# LAUNCHXL-F28069_B_1400922_5.net
KiCad netlist of a schematic drawn in Altium Designer
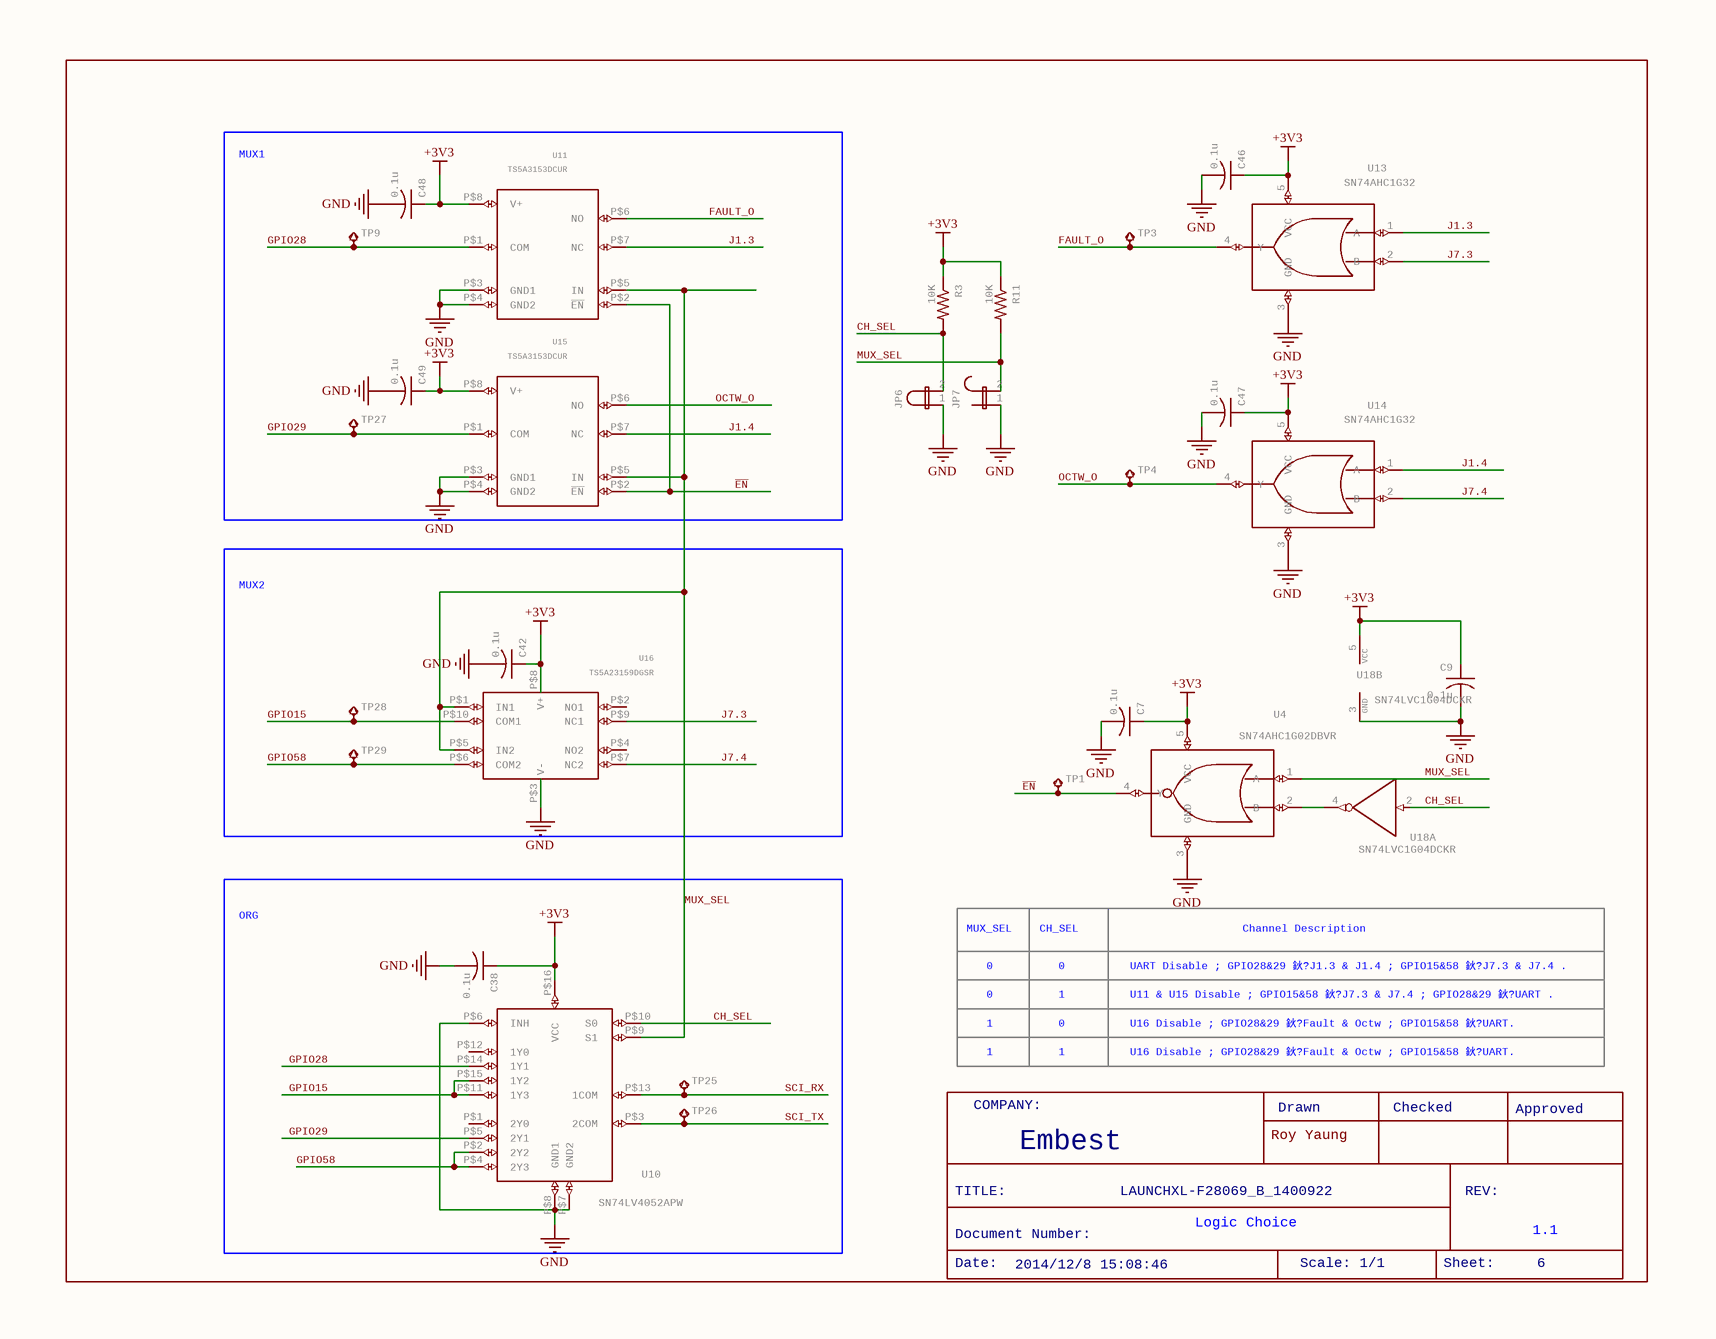
[diagram p0: LAUNCHXL-F28069_B_1400922_5.SchDoc]

(export (version "E")
  (design (tool "Eeschema 10.0.6"))
  (components
    (comp (ref "C7")
      (value "0.1u")
      (footprint "C0402")
      (description "CAPACITOR, American symbol")
      (libsource (lib "rcl") (part "C-USC0402"))
    )
    (comp (ref "C9")
      (value "0.1u")
      (footprint "C0402")
      (description "CAPACITOR, American symbol")
      (libsource (lib "rcl") (part "C-USC0402"))
    )
    (comp (ref "C38")
      (value "0.1u")
      (footprint "C0402")
      (description "CAPACITOR, American symbol")
      (libsource (lib "") (part "C-USC0402_1"))
    )
    (comp (ref "C42")
      (value "0.1u")
      (footprint "C0402")
      (description "CAPACITOR, American symbol")
      (libsource (lib "rcl") (part "C-USC0402"))
    )
    (comp (ref "C46")
      (value "0.1u")
      (footprint "C0402")
      (description "CAPACITOR, American symbol")
      (libsource (lib "rcl") (part "C-USC0402"))
    )
    (comp (ref "C47")
      (value "0.1u")
      (footprint "C0402")
      (description "CAPACITOR, American symbol")
      (libsource (lib "rcl") (part "C-USC0402"))
    )
    (comp (ref "C48")
      (value "0.1u")
      (footprint "C0402")
      (description "CAPACITOR, American symbol")
      (libsource (lib "rcl") (part "C-USC0402"))
    )
    (comp (ref "C49")
      (value "0.1u")
      (footprint "C0402")
      (description "CAPACITOR, American symbol")
      (libsource (lib "rcl") (part "C-USC0402"))
    )
    (comp (ref "JP6")
      (value "JP1ENORM")
      (footprint "JP1")
      (description "JUMPER")
      (libsource (lib "jumper") (part "JP1ENORM"))
    )
    (comp (ref "JP7")
      (value "JP1ENORM")
      (footprint "JP1")
      (description "JUMPER")
      (libsource (lib "jumper") (part "JP1ENORM"))
    )
    (comp (ref "R3")
      (value "10K")
      (footprint "R0402")
      (description "RESISTOR, American symbol")
      (libsource (lib "rcl") (part "R-US_R0402"))
    )
    (comp (ref "R11")
      (value "10K")
      (footprint "R0402")
      (description "RESISTOR, American symbol")
      (libsource (lib "rcl") (part "R-US_R0402"))
    )
    (comp (ref "TP1")
      (value "TESTPAD_TPB1,27")
      (footprint "TESTPAD_B1,27")
      (description "Test pad")
      (fields (field (name "LIBRARYNAME") "RF430FRL152H_EVM_a"))
      (libsource (lib "RF430FRL152H_EVM_a") (part "TESTPAD_TPB1,27"))
    )
    (comp (ref "TP3")
      (value "TESTPAD_TPB1,27")
      (footprint "TESTPAD_B1,27")
      (description "Test pad")
      (fields (field (name "LIBRARYNAME") "RF430FRL152H_EVM_a"))
      (libsource (lib "RF430FRL152H_EVM_a") (part "TESTPAD_TPB1,27"))
    )
    (comp (ref "TP4")
      (value "TESTPAD_TPB1,27")
      (footprint "TESTPAD_B1,27")
      (description "Test pad")
      (fields (field (name "LIBRARYNAME") "RF430FRL152H_EVM_a"))
      (libsource (lib "RF430FRL152H_EVM_a") (part "TESTPAD_TPB1,27"))
    )
    (comp (ref "TP9")
      (value "TESTPAD_TPB1,27")
      (footprint "TESTPAD_B1,27")
      (description "Test pad")
      (fields (field (name "LIBRARYNAME") "RF430FRL152H_EVM_a"))
      (libsource (lib "RF430FRL152H_EVM_a") (part "TESTPAD_TPB1,27"))
    )
    (comp (ref "TP25")
      (value "TESTPAD_TPB1,27")
      (footprint "TESTPAD_B1,27")
      (description "Test pad")
      (fields (field (name "LIBRARYNAME") "RF430FRL152H_EVM_a"))
      (libsource (lib "RF430FRL152H_EVM_a") (part "TESTPAD_TPB1,27"))
    )
    (comp (ref "TP26")
      (value "TESTPAD_TPB1,27")
      (footprint "TESTPAD_B1,27")
      (description "Test pad")
      (fields (field (name "LIBRARYNAME") "RF430FRL152H_EVM_a"))
      (libsource (lib "RF430FRL152H_EVM_a") (part "TESTPAD_TPB1,27"))
    )
    (comp (ref "TP27")
      (value "TESTPAD_TPB1,27")
      (footprint "TESTPAD_B1,27")
      (description "Test pad")
      (fields (field (name "LIBRARYNAME") "RF430FRL152H_EVM_a"))
      (libsource (lib "RF430FRL152H_EVM_a") (part "TESTPAD_TPB1,27"))
    )
    (comp (ref "TP28")
      (value "TESTPAD_TPB1,27")
      (footprint "TESTPAD_B1,27")
      (description "Test pad")
      (fields (field (name "LIBRARYNAME") "RF430FRL152H_EVM_a"))
      (libsource (lib "RF430FRL152H_EVM_a") (part "TESTPAD_TPB1,27"))
    )
    (comp (ref "TP29")
      (value "TESTPAD_TPB1,27")
      (footprint "TESTPAD_B1,27")
      (description "Test pad")
      (fields (field (name "LIBRARYNAME") "RF430FRL152H_EVM_a"))
      (libsource (lib "RF430FRL152H_EVM_a") (part "TESTPAD_TPB1,27"))
    )
    (comp (ref "U$1")
      (value "ROY_JUMPER")
      (footprint "ROY_JUMPER")
      (libsource (lib "roy") (part "ROY_JUMPER"))
    )
    (comp (ref "U$2")
      (value "ROY_JUMPER")
      (footprint "ROY_JUMPER")
      (libsource (lib "roy") (part "ROY_JUMPER"))
    )
    (comp (ref "U4")
      (value "SN74AHC1G02DBVR")
      (footprint "SOT23-5-DBV")
      (libsource (lib "LAUNCHXL-F28027") (part "SN74AHC1G02"))
    )
    (comp (ref "U10")
      (value "SN74LV4052APW")
      (footprint "TSSOP16-PW")
      (libsource (lib "LAUNCHXL-F28027") (part "SN74LV4052APW"))
    )
    (comp (ref "U11")
      (value "TS5A3153DCUR")
      (footprint "TI-DCU8")
      (libsource (lib "LAUNCHXL-F28027") (part "TS5A3153DCUR"))
    )
    (comp (ref "U13")
      (value "SN74AHC1G32")
      (footprint "SOT23-5-DBV")
      (libsource (lib "LAUNCHXL-F28027") (part "SN74AHC1G32"))
    )
    (comp (ref "U14")
      (value "SN74AHC1G32")
      (footprint "SOT23-5-DBV")
      (libsource (lib "LAUNCHXL-F28027") (part "SN74AHC1G32"))
    )
    (comp (ref "U15")
      (value "TS5A3153DCUR")
      (footprint "TI-DCU8")
      (libsource (lib "LAUNCHXL-F28027") (part "TS5A3153DCUR"))
    )
    (comp (ref "U16")
      (value "TS5A23159DGSR")
      (footprint "TI-DGS10")
      (libsource (lib "LAUNCHXL-F28027") (part "TS5A23159DGSR"))
    )
    (comp (ref "U18")
      (value "SN74LVC1G04DCKR")
      (footprint "74XX-LITTLE-DE_SC70-5")
      (description "INVERTER Gate")
      (fields
        (field (name "GND") "GND")
        (field (name "VCC") "VCC")
        (field (name "LIBRARYNAME") "RF430FRL152H_EVM_a")
      )
      (libsource (lib "RF430FRL152H_EVM_a") (part "74XX-LITTLE-DE_74*1G04DCK"))
    )
  )
  (nets
    (net (code "1") (name "+3V3") (class "Default")
      (node (ref "C38") (pin "1") (pinfunction "1_1") (pintype "passive"))
      (node (ref "C42") (pin "1") (pinfunction "1_1") (pintype "passive"))
      (node (ref "C46") (pin "1") (pinfunction "1_1") (pintype "passive"))
      (node (ref "C47") (pin "1") (pinfunction "1_1") (pintype "passive"))
      (node (ref "C48") (pin "1") (pinfunction "1_1") (pintype "passive"))
      (node (ref "C49") (pin "1") (pinfunction "1_1") (pintype "passive"))
      (node (ref "C7") (pin "1") (pinfunction "1_1") (pintype "passive"))
      (node (ref "C9") (pin "1") (pinfunction "1_1") (pintype "passive"))
      (node (ref "R11") (pin "1") (pinfunction "1_1") (pintype "passive"))
      (node (ref "R3") (pin "1") (pinfunction "1_1") (pintype "passive"))
      (node (ref "U10") (pin "P$16") (pinfunction "VCC_P$16") (pintype "bidirectional"))
      (node (ref "U11") (pin "P$8") (pinfunction "V+_P$8") (pintype "bidirectional"))
      (node (ref "U13") (pin "5") (pinfunction "VCC_5") (pintype "bidirectional"))
      (node (ref "U14") (pin "5") (pinfunction "VCC_5") (pintype "bidirectional"))
      (node (ref "U15") (pin "P$8") (pinfunction "V+_P$8") (pintype "bidirectional"))
      (node (ref "U16") (pin "P$8") (pinfunction "V+_P$8") (pintype "bidirectional"))
      (node (ref "U18") (pin "5") (pinfunction "VCC_5") (pintype "power_in"))
      (node (ref "U4") (pin "5") (pinfunction "VCC_5") (pintype "bidirectional"))
    )
    (net (code "2") (name "/CH_SEL") (class "Default")
      (node (ref "JP6") (pin "2") (pinfunction "2_2") (pintype "passive"))
      (node (ref "R3") (pin "2") (pinfunction "2_2") (pintype "passive"))
      (node (ref "U10") (pin "P$10") (pinfunction "S0_P$10") (pintype "bidirectional"))
      (node (ref "U18") (pin "2") (pinfunction "I_2") (pintype "input"))
    )
    (net (code "3") (name "/FAULT_O") (class "Default")
      (node (ref "TP3") (pin "TP") (pinfunction "TP_TP") (pintype "input"))
      (node (ref "U11") (pin "P$6") (pinfunction "NO_P$6") (pintype "bidirectional"))
      (node (ref "U13") (pin "4") (pinfunction "Y_4") (pintype "bidirectional"))
    )
    (net (code "4") (name "/GPIO15") (class "Default")
      (node (ref "TP28") (pin "TP") (pinfunction "TP_TP") (pintype "input"))
      (node (ref "U10") (pin "P$11") (pinfunction "1Y3_P$11") (pintype "bidirectional"))
      (node (ref "U10") (pin "P$15") (pinfunction "1Y2_P$15") (pintype "bidirectional"))
      (node (ref "U16") (pin "P$10") (pinfunction "COM1_P$10") (pintype "bidirectional"))
    )
    (net (code "5") (name "/GPIO28") (class "Default")
      (node (ref "TP9") (pin "TP") (pinfunction "TP_TP") (pintype "input"))
      (node (ref "U10") (pin "P$14") (pinfunction "1Y1_P$14") (pintype "bidirectional"))
      (node (ref "U11") (pin "P$1") (pinfunction "COM_P$1") (pintype "bidirectional"))
    )
    (net (code "6") (name "/GPIO29") (class "Default")
      (node (ref "TP27") (pin "TP") (pinfunction "TP_TP") (pintype "input"))
      (node (ref "U10") (pin "P$5") (pinfunction "2Y1_P$5") (pintype "bidirectional"))
      (node (ref "U15") (pin "P$1") (pinfunction "COM_P$1") (pintype "bidirectional"))
    )
    (net (code "7") (name "/GPIO58") (class "Default")
      (node (ref "TP29") (pin "TP") (pinfunction "TP_TP") (pintype "input"))
      (node (ref "U10") (pin "P$2") (pinfunction "2Y2_P$2") (pintype "bidirectional"))
      (node (ref "U10") (pin "P$4") (pinfunction "2Y3_P$4") (pintype "bidirectional"))
      (node (ref "U16") (pin "P$6") (pinfunction "COM2_P$6") (pintype "bidirectional"))
    )
    (net (code "8") (name "/J1.3") (class "Default")
      (node (ref "U11") (pin "P$7") (pinfunction "NC_P$7") (pintype "bidirectional"))
      (node (ref "U13") (pin "1") (pinfunction "A_1") (pintype "bidirectional"))
    )
    (net (code "9") (name "/J1.4") (class "Default")
      (node (ref "U14") (pin "1") (pinfunction "A_1") (pintype "bidirectional"))
      (node (ref "U15") (pin "P$7") (pinfunction "NC_P$7") (pintype "bidirectional"))
    )
    (net (code "10") (name "/J7.3") (class "Default")
      (node (ref "U13") (pin "2") (pinfunction "B_2") (pintype "bidirectional"))
      (node (ref "U16") (pin "P$9") (pinfunction "NC1_P$9") (pintype "bidirectional"))
    )
    (net (code "11") (name "/J7.4") (class "Default")
      (node (ref "U14") (pin "2") (pinfunction "B_2") (pintype "bidirectional"))
      (node (ref "U16") (pin "P$7") (pinfunction "NC2_P$7") (pintype "bidirectional"))
    )
    (net (code "12") (name "/MUX_SEL") (class "Default")
      (node (ref "JP7") (pin "2") (pinfunction "2_2") (pintype "passive"))
      (node (ref "R11") (pin "2") (pinfunction "2_2") (pintype "passive"))
      (node (ref "U10") (pin "P$9") (pinfunction "S1_P$9") (pintype "bidirectional"))
      (node (ref "U11") (pin "P$5") (pinfunction "IN_P$5") (pintype "bidirectional"))
      (node (ref "U15") (pin "P$5") (pinfunction "IN_P$5") (pintype "bidirectional"))
      (node (ref "U16") (pin "P$1") (pinfunction "IN1_P$1") (pintype "bidirectional"))
      (node (ref "U16") (pin "P$5") (pinfunction "IN2_P$5") (pintype "bidirectional"))
      (node (ref "U4") (pin "1") (pinfunction "A_1") (pintype "bidirectional"))
    )
    (net (code "13") (name "/OCTW_O") (class "Default")
      (node (ref "TP4") (pin "TP") (pinfunction "TP_TP") (pintype "input"))
      (node (ref "U14") (pin "4") (pinfunction "Y_4") (pintype "bidirectional"))
      (node (ref "U15") (pin "P$6") (pinfunction "NO_P$6") (pintype "bidirectional"))
    )
    (net (code "14") (name "/SCI_RX") (class "Default")
      (node (ref "TP25") (pin "TP") (pinfunction "TP_TP") (pintype "input"))
      (node (ref "U10") (pin "P$13") (pinfunction "1COM_P$13") (pintype "bidirectional"))
    )
    (net (code "15") (name "/SCI_TX") (class "Default")
      (node (ref "TP26") (pin "TP") (pinfunction "TP_TP") (pintype "input"))
      (node (ref "U10") (pin "P$3") (pinfunction "2COM_P$3") (pintype "bidirectional"))
    )
    (net (code "16") (name "/~{EN}") (class "Default")
      (node (ref "TP1") (pin "TP") (pinfunction "TP_TP") (pintype "input"))
      (node (ref "U11") (pin "P$2") (pinfunction "~{EN}_P$2") (pintype "bidirectional"))
      (node (ref "U15") (pin "P$2") (pinfunction "~{EN}_P$2") (pintype "bidirectional"))
      (node (ref "U4") (pin "4") (pinfunction "Y_4") (pintype "bidirectional"))
    )
    (net (code "17") (name "GND") (class "Default")
      (node (ref "C38") (pin "2") (pinfunction "2_2") (pintype "passive"))
      (node (ref "C42") (pin "2") (pinfunction "2_2") (pintype "passive"))
      (node (ref "C46") (pin "2") (pinfunction "2_2") (pintype "passive"))
      (node (ref "C47") (pin "2") (pinfunction "2_2") (pintype "passive"))
      (node (ref "C48") (pin "2") (pinfunction "2_2") (pintype "passive"))
      (node (ref "C49") (pin "2") (pinfunction "2_2") (pintype "passive"))
      (node (ref "C7") (pin "2") (pinfunction "2_2") (pintype "passive"))
      (node (ref "C9") (pin "2") (pinfunction "2_2") (pintype "passive"))
      (node (ref "JP6") (pin "1") (pinfunction "1_1") (pintype "passive"))
      (node (ref "JP7") (pin "1") (pinfunction "1_1") (pintype "passive"))
      (node (ref "U10") (pin "P$6") (pinfunction "INH_P$6") (pintype "bidirectional"))
      (node (ref "U10") (pin "P$7") (pinfunction "GND2_P$7") (pintype "bidirectional"))
      (node (ref "U10") (pin "P$8") (pinfunction "GND1_P$8") (pintype "bidirectional"))
      (node (ref "U11") (pin "P$3") (pinfunction "GND1_P$3") (pintype "bidirectional"))
      (node (ref "U11") (pin "P$4") (pinfunction "GND2_P$4") (pintype "bidirectional"))
      (node (ref "U13") (pin "3") (pinfunction "GND_3") (pintype "bidirectional"))
      (node (ref "U14") (pin "3") (pinfunction "GND_3") (pintype "bidirectional"))
      (node (ref "U15") (pin "P$3") (pinfunction "GND1_P$3") (pintype "bidirectional"))
      (node (ref "U15") (pin "P$4") (pinfunction "GND2_P$4") (pintype "bidirectional"))
      (node (ref "U16") (pin "P$3") (pinfunction "V-_P$3") (pintype "bidirectional"))
      (node (ref "U18") (pin "3") (pinfunction "GND_3") (pintype "power_in"))
      (node (ref "U4") (pin "3") (pinfunction "GND_3") (pintype "bidirectional"))
    )
    (net (code "18") (name "Net-(U18A-O)") (class "Default")
      (node (ref "U18") (pin "4") (pinfunction "O_4") (pintype "output"))
      (node (ref "U4") (pin "2") (pinfunction "B_2") (pintype "bidirectional"))
    )
    (net (code "19") (name "unconnected-(U10-1Y0-PadP$12)") (class "Default")
      (node (ref "U10") (pin "P$12") (pinfunction "1Y0_P$12") (pintype "bidirectional"))
    )
    (net (code "20") (name "unconnected-(U10-2Y0-PadP$1)") (class "Default")
      (node (ref "U10") (pin "P$1") (pinfunction "2Y0_P$1") (pintype "bidirectional"))
    )
    (net (code "21") (name "unconnected-(U16-NO1-PadP$2)") (class "Default")
      (node (ref "U16") (pin "P$2") (pinfunction "NO1_P$2") (pintype "bidirectional"))
    )
    (net (code "22") (name "unconnected-(U16-NO2-PadP$4)") (class "Default")
      (node (ref "U16") (pin "P$4") (pinfunction "NO2_P$4") (pintype "bidirectional"))
    )
  )
)
